# MCU_Comparison.net
KiCad netlist of a schematic drawn in Altium Designer
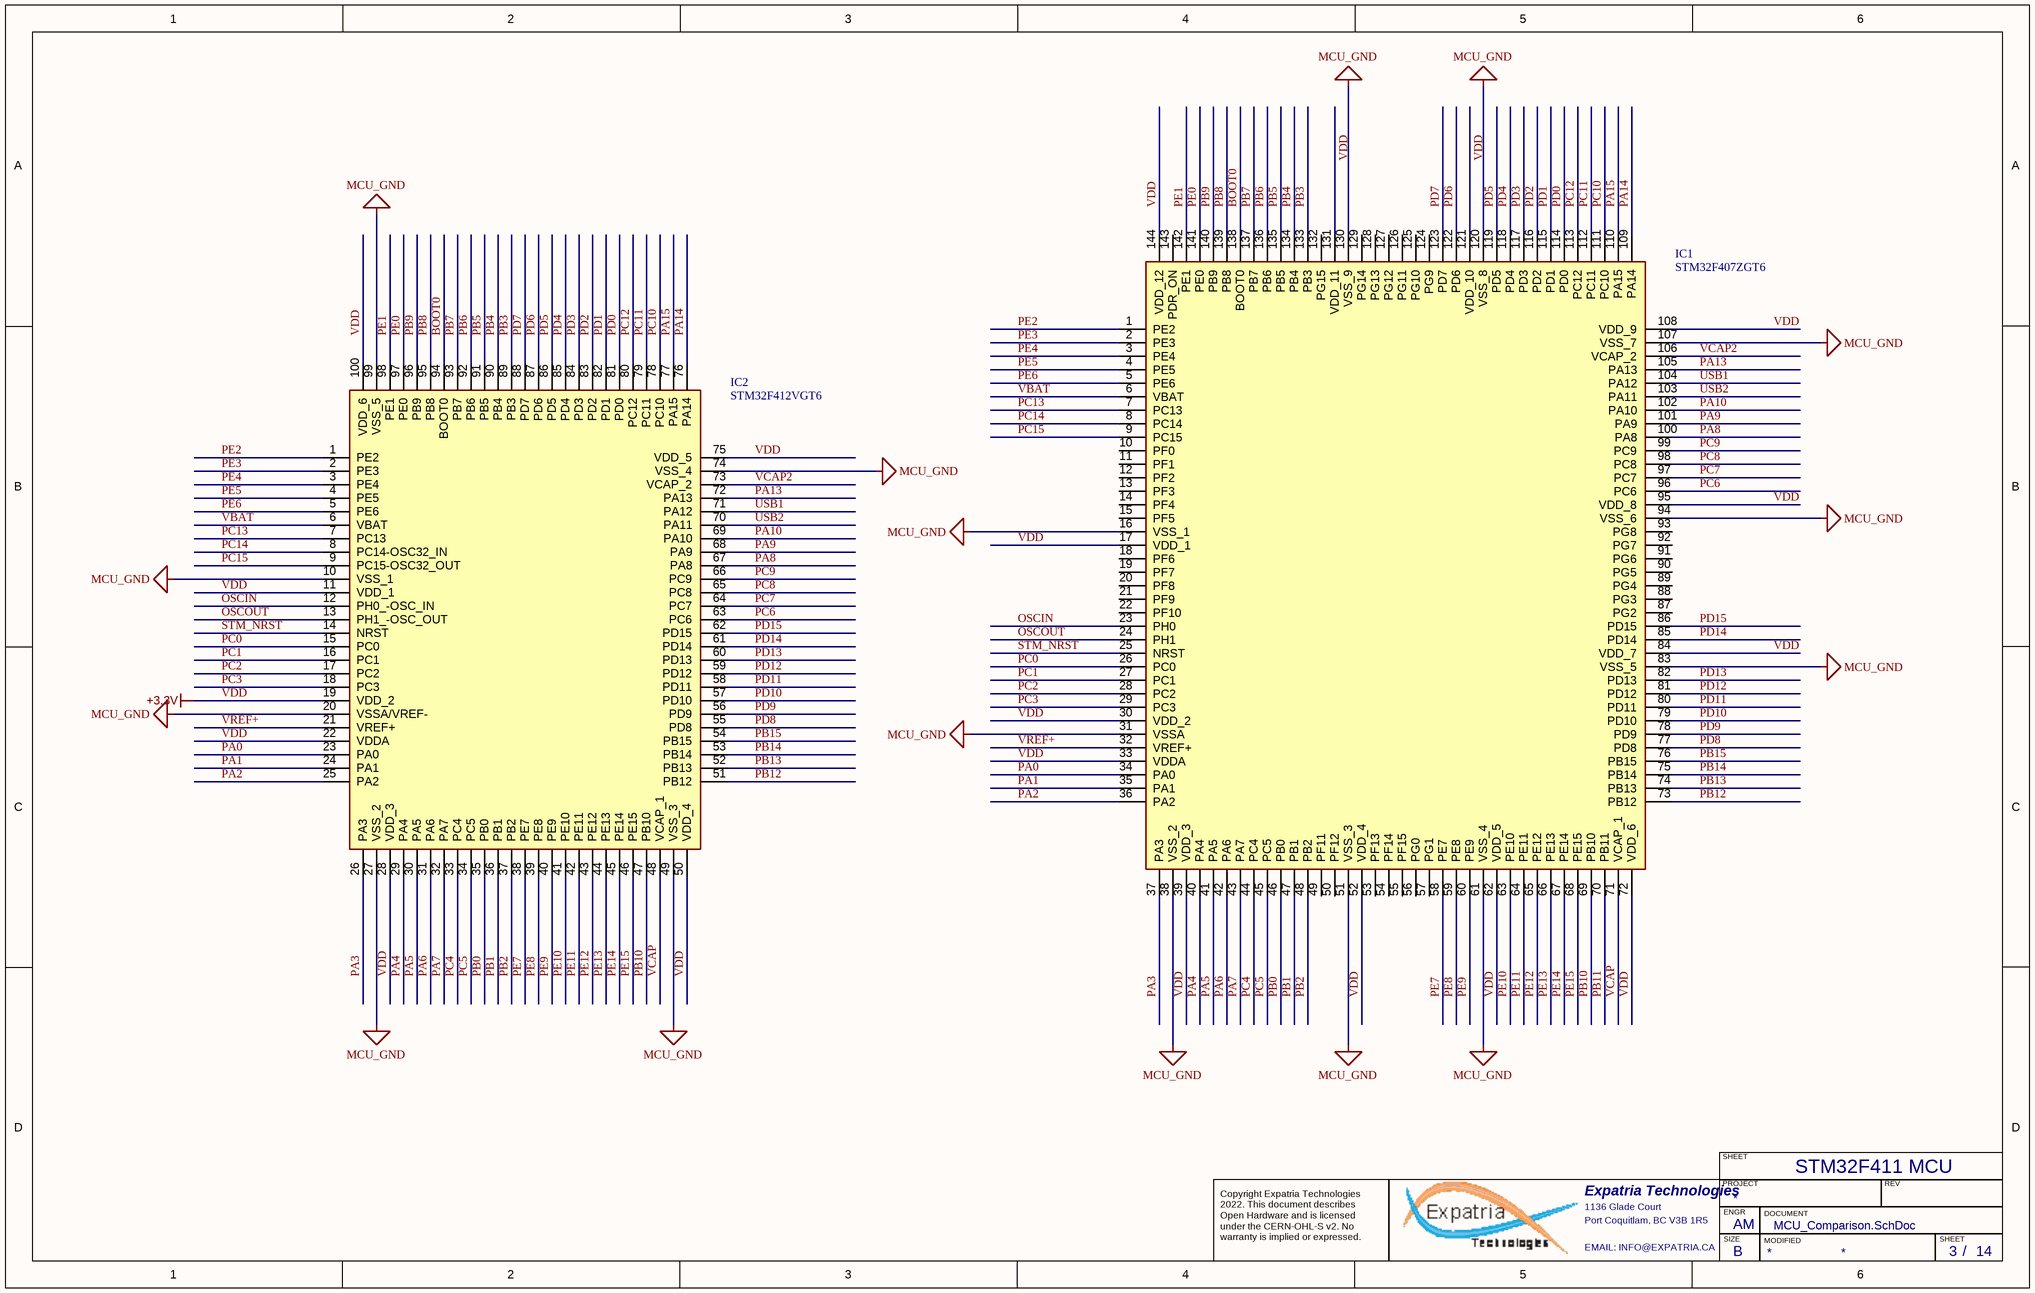
[diagram p0: MCU_Comparison.SchDoc]

(export (version "E")
  (design (tool "Eeschema 10.0.6"))
  (components
    (comp (ref "IC1")
      (value "STM32F407ZGT6")
      (footprint "SamacSys:QFP50P2200X2200X160-144N")
      (description "Integrated Circuit")
      (fields (field (name "MOUSER PART NUMBER") "511-STM32F407ZGT6"))
      (libsource (lib "*") (part "STM32F407ZGT6"))
    )
    (comp (ref "IC2")
      (value "STM32F412VGT6")
      (footprint "SamacSys:QFP50P1600X1600X160-100N")
      (description "Integrated Circuit")
      (fields (field (name "MOUSER PART NUMBER") "511-STM32F412VGT6"))
      (libsource (lib "*") (part "STM32F412VGT6"))
    )
  )
  (nets
    (net (code "1") (name "+3.3V") (class "Default")
      (node (ref "IC1") (pin "108") (pinfunction "VDD_9_108") (pintype "passive"))
      (node (ref "IC1") (pin "121") (pinfunction "VDD_10_121") (pintype "passive"))
      (node (ref "IC1") (pin "131") (pinfunction "VDD_11_131") (pintype "passive"))
      (node (ref "IC1") (pin "144") (pinfunction "VDD_12_144") (pintype "passive"))
      (node (ref "IC1") (pin "17") (pinfunction "VDD_1_17") (pintype "passive"))
      (node (ref "IC1") (pin "30") (pinfunction "VDD_2_30") (pintype "passive"))
      (node (ref "IC1") (pin "33") (pinfunction "VDDA_33") (pintype "passive"))
      (node (ref "IC1") (pin "39") (pinfunction "VDD_3_39") (pintype "passive"))
      (node (ref "IC1") (pin "52") (pinfunction "VDD_4_52") (pintype "passive"))
      (node (ref "IC1") (pin "62") (pinfunction "VDD_5_62") (pintype "passive"))
      (node (ref "IC1") (pin "72") (pinfunction "VDD_6_72") (pintype "passive"))
      (node (ref "IC1") (pin "84") (pinfunction "VDD_7_84") (pintype "passive"))
      (node (ref "IC1") (pin "95") (pinfunction "VDD_8_95") (pintype "passive"))
      (node (ref "IC2") (pin "100") (pinfunction "VDD_6_100") (pintype "passive"))
      (node (ref "IC2") (pin "11") (pinfunction "VDD_1_11") (pintype "passive"))
      (node (ref "IC2") (pin "19") (pinfunction "VDD_2_19") (pintype "passive"))
      (node (ref "IC2") (pin "22") (pinfunction "VDDA_22") (pintype "passive"))
      (node (ref "IC2") (pin "28") (pinfunction "VDD_3_28") (pintype "passive"))
      (node (ref "IC2") (pin "50") (pinfunction "VDD_4_50") (pintype "passive"))
      (node (ref "IC2") (pin "75") (pinfunction "VDD_5_75") (pintype "passive"))
    )
    (net (code "2") (name "/BOOT0") (class "Default")
      (node (ref "IC1") (pin "138") (pinfunction "BOOT0_138") (pintype "passive"))
      (node (ref "IC2") (pin "94") (pinfunction "BOOT0_94") (pintype "passive"))
    )
    (net (code "3") (name "/OSCIN") (class "Default")
      (node (ref "IC1") (pin "23") (pinfunction "PH0_23") (pintype "passive"))
      (node (ref "IC2") (pin "12") (pinfunction "PH0_-OSC_IN_12") (pintype "passive"))
    )
    (net (code "4") (name "/OSCOUT") (class "Default")
      (node (ref "IC1") (pin "24") (pinfunction "PH1_24") (pintype "passive"))
      (node (ref "IC2") (pin "13") (pinfunction "PH1_-OSC_OUT_13") (pintype "passive"))
    )
    (net (code "5") (name "/PA0") (class "Default")
      (node (ref "IC1") (pin "34") (pinfunction "PA0_34") (pintype "passive"))
      (node (ref "IC2") (pin "23") (pinfunction "PA0_23") (pintype "passive"))
    )
    (net (code "6") (name "/PA1") (class "Default")
      (node (ref "IC1") (pin "35") (pinfunction "PA1_35") (pintype "passive"))
      (node (ref "IC2") (pin "24") (pinfunction "PA1_24") (pintype "passive"))
    )
    (net (code "7") (name "/PA2") (class "Default")
      (node (ref "IC1") (pin "36") (pinfunction "PA2_36") (pintype "passive"))
      (node (ref "IC2") (pin "25") (pinfunction "PA2_25") (pintype "passive"))
    )
    (net (code "8") (name "/PA3") (class "Default")
      (node (ref "IC1") (pin "37") (pinfunction "PA3_37") (pintype "passive"))
      (node (ref "IC2") (pin "26") (pinfunction "PA3_26") (pintype "passive"))
    )
    (net (code "9") (name "/PA4") (class "Default")
      (node (ref "IC1") (pin "40") (pinfunction "PA4_40") (pintype "passive"))
      (node (ref "IC2") (pin "29") (pinfunction "PA4_29") (pintype "passive"))
    )
    (net (code "10") (name "/PA5") (class "Default")
      (node (ref "IC1") (pin "41") (pinfunction "PA5_41") (pintype "passive"))
      (node (ref "IC2") (pin "30") (pinfunction "PA5_30") (pintype "passive"))
    )
    (net (code "11") (name "/PA6") (class "Default")
      (node (ref "IC1") (pin "42") (pinfunction "PA6_42") (pintype "passive"))
      (node (ref "IC2") (pin "31") (pinfunction "PA6_31") (pintype "passive"))
    )
    (net (code "12") (name "/PA7") (class "Default")
      (node (ref "IC1") (pin "43") (pinfunction "PA7_43") (pintype "passive"))
      (node (ref "IC2") (pin "32") (pinfunction "PA7_32") (pintype "passive"))
    )
    (net (code "13") (name "/PA8") (class "Default")
      (node (ref "IC1") (pin "100") (pinfunction "PA8_100") (pintype "passive"))
      (node (ref "IC2") (pin "67") (pinfunction "PA8_67") (pintype "passive"))
    )
    (net (code "14") (name "/PA9") (class "Default")
      (node (ref "IC1") (pin "101") (pinfunction "PA9_101") (pintype "passive"))
      (node (ref "IC2") (pin "68") (pinfunction "PA9_68") (pintype "passive"))
    )
    (net (code "15") (name "/PA10") (class "Default")
      (node (ref "IC1") (pin "102") (pinfunction "PA10_102") (pintype "passive"))
      (node (ref "IC2") (pin "69") (pinfunction "PA10_69") (pintype "passive"))
    )
    (net (code "16") (name "/PA13") (class "Default")
      (node (ref "IC1") (pin "105") (pinfunction "PA13_105") (pintype "passive"))
      (node (ref "IC2") (pin "72") (pinfunction "PA13_72") (pintype "passive"))
    )
    (net (code "17") (name "/PA14") (class "Default")
      (node (ref "IC1") (pin "109") (pinfunction "PA14_109") (pintype "passive"))
      (node (ref "IC2") (pin "76") (pinfunction "PA14_76") (pintype "passive"))
    )
    (net (code "18") (name "/PA15") (class "Default")
      (node (ref "IC1") (pin "110") (pinfunction "PA15_110") (pintype "passive"))
      (node (ref "IC2") (pin "77") (pinfunction "PA15_77") (pintype "passive"))
    )
    (net (code "19") (name "/PB0") (class "Default")
      (node (ref "IC1") (pin "46") (pinfunction "PB0_46") (pintype "passive"))
      (node (ref "IC2") (pin "35") (pinfunction "PB0_35") (pintype "passive"))
    )
    (net (code "20") (name "/PB1") (class "Default")
      (node (ref "IC1") (pin "47") (pinfunction "PB1_47") (pintype "passive"))
      (node (ref "IC2") (pin "36") (pinfunction "PB1_36") (pintype "passive"))
    )
    (net (code "21") (name "/PB2") (class "Default")
      (node (ref "IC1") (pin "48") (pinfunction "PB2_48") (pintype "passive"))
      (node (ref "IC2") (pin "37") (pinfunction "PB2_37") (pintype "passive"))
    )
    (net (code "22") (name "/PB3") (class "Default")
      (node (ref "IC1") (pin "133") (pinfunction "PB3_133") (pintype "passive"))
      (node (ref "IC2") (pin "89") (pinfunction "PB3_89") (pintype "passive"))
    )
    (net (code "23") (name "/PB4") (class "Default")
      (node (ref "IC1") (pin "134") (pinfunction "PB4_134") (pintype "passive"))
      (node (ref "IC2") (pin "90") (pinfunction "PB4_90") (pintype "passive"))
    )
    (net (code "24") (name "/PB5") (class "Default")
      (node (ref "IC1") (pin "135") (pinfunction "PB5_135") (pintype "passive"))
      (node (ref "IC2") (pin "91") (pinfunction "PB5_91") (pintype "passive"))
    )
    (net (code "25") (name "/PB6") (class "Default")
      (node (ref "IC1") (pin "136") (pinfunction "PB6_136") (pintype "passive"))
      (node (ref "IC2") (pin "92") (pinfunction "PB6_92") (pintype "passive"))
    )
    (net (code "26") (name "/PB7") (class "Default")
      (node (ref "IC1") (pin "137") (pinfunction "PB7_137") (pintype "passive"))
      (node (ref "IC2") (pin "93") (pinfunction "PB7_93") (pintype "passive"))
    )
    (net (code "27") (name "/PB8") (class "Default")
      (node (ref "IC1") (pin "139") (pinfunction "PB8_139") (pintype "passive"))
      (node (ref "IC2") (pin "95") (pinfunction "PB8_95") (pintype "passive"))
    )
    (net (code "28") (name "/PB9") (class "Default")
      (node (ref "IC1") (pin "140") (pinfunction "PB9_140") (pintype "passive"))
      (node (ref "IC2") (pin "96") (pinfunction "PB9_96") (pintype "passive"))
    )
    (net (code "29") (name "/PB10") (class "Default")
      (node (ref "IC1") (pin "69") (pinfunction "PB10_69") (pintype "passive"))
      (node (ref "IC2") (pin "47") (pinfunction "PB10_47") (pintype "passive"))
    )
    (net (code "30") (name "/PB11") (class "Default")
      (node (ref "IC1") (pin "70") (pinfunction "PB11_70") (pintype "passive"))
    )
    (net (code "31") (name "/PB12") (class "Default")
      (node (ref "IC1") (pin "73") (pinfunction "PB12_73") (pintype "passive"))
      (node (ref "IC2") (pin "51") (pinfunction "PB12_51") (pintype "passive"))
    )
    (net (code "32") (name "/PB13") (class "Default")
      (node (ref "IC1") (pin "74") (pinfunction "PB13_74") (pintype "passive"))
      (node (ref "IC2") (pin "52") (pinfunction "PB13_52") (pintype "passive"))
    )
    (net (code "33") (name "/PB14") (class "Default")
      (node (ref "IC1") (pin "75") (pinfunction "PB14_75") (pintype "passive"))
      (node (ref "IC2") (pin "53") (pinfunction "PB14_53") (pintype "passive"))
    )
    (net (code "34") (name "/PB15") (class "Default")
      (node (ref "IC1") (pin "76") (pinfunction "PB15_76") (pintype "passive"))
      (node (ref "IC2") (pin "54") (pinfunction "PB15_54") (pintype "passive"))
    )
    (net (code "35") (name "/PC0") (class "Default")
      (node (ref "IC1") (pin "26") (pinfunction "PC0_26") (pintype "passive"))
      (node (ref "IC2") (pin "15") (pinfunction "PC0_15") (pintype "passive"))
    )
    (net (code "36") (name "/PC1") (class "Default")
      (node (ref "IC1") (pin "27") (pinfunction "PC1_27") (pintype "passive"))
      (node (ref "IC2") (pin "16") (pinfunction "PC1_16") (pintype "passive"))
    )
    (net (code "37") (name "/PC2") (class "Default")
      (node (ref "IC1") (pin "28") (pinfunction "PC2_28") (pintype "passive"))
      (node (ref "IC2") (pin "17") (pinfunction "PC2_17") (pintype "passive"))
    )
    (net (code "38") (name "/PC3") (class "Default")
      (node (ref "IC1") (pin "29") (pinfunction "PC3_29") (pintype "passive"))
      (node (ref "IC2") (pin "18") (pinfunction "PC3_18") (pintype "passive"))
    )
    (net (code "39") (name "/PC4") (class "Default")
      (node (ref "IC1") (pin "44") (pinfunction "PC4_44") (pintype "passive"))
      (node (ref "IC2") (pin "33") (pinfunction "PC4_33") (pintype "passive"))
    )
    (net (code "40") (name "/PC5") (class "Default")
      (node (ref "IC1") (pin "45") (pinfunction "PC5_45") (pintype "passive"))
      (node (ref "IC2") (pin "34") (pinfunction "PC5_34") (pintype "passive"))
    )
    (net (code "41") (name "/PC6") (class "Default")
      (node (ref "IC1") (pin "96") (pinfunction "PC6_96") (pintype "passive"))
      (node (ref "IC2") (pin "63") (pinfunction "PC6_63") (pintype "passive"))
    )
    (net (code "42") (name "/PC7") (class "Default")
      (node (ref "IC1") (pin "97") (pinfunction "PC7_97") (pintype "passive"))
      (node (ref "IC2") (pin "64") (pinfunction "PC7_64") (pintype "passive"))
    )
    (net (code "43") (name "/PC8") (class "Default")
      (node (ref "IC1") (pin "98") (pinfunction "PC8_98") (pintype "passive"))
      (node (ref "IC2") (pin "65") (pinfunction "PC8_65") (pintype "passive"))
    )
    (net (code "44") (name "/PC9") (class "Default")
      (node (ref "IC1") (pin "99") (pinfunction "PC9_99") (pintype "passive"))
      (node (ref "IC2") (pin "66") (pinfunction "PC9_66") (pintype "passive"))
    )
    (net (code "45") (name "/PC10") (class "Default")
      (node (ref "IC1") (pin "111") (pinfunction "PC10_111") (pintype "passive"))
      (node (ref "IC2") (pin "78") (pinfunction "PC10_78") (pintype "passive"))
    )
    (net (code "46") (name "/PC11") (class "Default")
      (node (ref "IC1") (pin "112") (pinfunction "PC11_112") (pintype "passive"))
      (node (ref "IC2") (pin "79") (pinfunction "PC11_79") (pintype "passive"))
    )
    (net (code "47") (name "/PC12") (class "Default")
      (node (ref "IC1") (pin "113") (pinfunction "PC12_113") (pintype "passive"))
      (node (ref "IC2") (pin "80") (pinfunction "PC12_80") (pintype "passive"))
    )
    (net (code "48") (name "/PC13") (class "Default")
      (node (ref "IC1") (pin "7") (pinfunction "PC13_7") (pintype "passive"))
      (node (ref "IC2") (pin "7") (pinfunction "PC13_7") (pintype "passive"))
    )
    (net (code "49") (name "/PC14") (class "Default")
      (node (ref "IC1") (pin "8") (pinfunction "PC14_8") (pintype "passive"))
      (node (ref "IC2") (pin "8") (pinfunction "PC14-OSC32_IN_8") (pintype "passive"))
    )
    (net (code "50") (name "/PC15") (class "Default")
      (node (ref "IC1") (pin "9") (pinfunction "PC15_9") (pintype "passive"))
      (node (ref "IC2") (pin "9") (pinfunction "PC15-OSC32_OUT_9") (pintype "passive"))
    )
    (net (code "51") (name "/PD0") (class "Default")
      (node (ref "IC1") (pin "114") (pinfunction "PD0_114") (pintype "passive"))
      (node (ref "IC2") (pin "81") (pinfunction "PD0_81") (pintype "passive"))
    )
    (net (code "52") (name "/PD1") (class "Default")
      (node (ref "IC1") (pin "115") (pinfunction "PD1_115") (pintype "passive"))
      (node (ref "IC2") (pin "82") (pinfunction "PD1_82") (pintype "passive"))
    )
    (net (code "53") (name "/PD2") (class "Default")
      (node (ref "IC1") (pin "116") (pinfunction "PD2_116") (pintype "passive"))
      (node (ref "IC2") (pin "83") (pinfunction "PD2_83") (pintype "passive"))
    )
    (net (code "54") (name "/PD3") (class "Default")
      (node (ref "IC1") (pin "117") (pinfunction "PD3_117") (pintype "passive"))
      (node (ref "IC2") (pin "84") (pinfunction "PD3_84") (pintype "passive"))
    )
    (net (code "55") (name "/PD4") (class "Default")
      (node (ref "IC1") (pin "118") (pinfunction "PD4_118") (pintype "passive"))
      (node (ref "IC2") (pin "85") (pinfunction "PD4_85") (pintype "passive"))
    )
    (net (code "56") (name "/PD5") (class "Default")
      (node (ref "IC1") (pin "119") (pinfunction "PD5_119") (pintype "passive"))
      (node (ref "IC2") (pin "86") (pinfunction "PD5_86") (pintype "passive"))
    )
    (net (code "57") (name "/PD6") (class "Default")
      (node (ref "IC1") (pin "122") (pinfunction "PD6_122") (pintype "passive"))
      (node (ref "IC2") (pin "87") (pinfunction "PD6_87") (pintype "passive"))
    )
    (net (code "58") (name "/PD7") (class "Default")
      (node (ref "IC1") (pin "123") (pinfunction "PD7_123") (pintype "passive"))
      (node (ref "IC2") (pin "88") (pinfunction "PD7_88") (pintype "passive"))
    )
    (net (code "59") (name "/PD8") (class "Default")
      (node (ref "IC1") (pin "77") (pinfunction "PD8_77") (pintype "passive"))
      (node (ref "IC2") (pin "55") (pinfunction "PD8_55") (pintype "passive"))
    )
    (net (code "60") (name "/PD9") (class "Default")
      (node (ref "IC1") (pin "78") (pinfunction "PD9_78") (pintype "passive"))
      (node (ref "IC2") (pin "56") (pinfunction "PD9_56") (pintype "passive"))
    )
    (net (code "61") (name "/PD10") (class "Default")
      (node (ref "IC1") (pin "79") (pinfunction "PD10_79") (pintype "passive"))
      (node (ref "IC2") (pin "57") (pinfunction "PD10_57") (pintype "passive"))
    )
    (net (code "62") (name "/PD11") (class "Default")
      (node (ref "IC1") (pin "80") (pinfunction "PD11_80") (pintype "passive"))
      (node (ref "IC2") (pin "58") (pinfunction "PD11_58") (pintype "passive"))
    )
    (net (code "63") (name "/PD12") (class "Default")
      (node (ref "IC1") (pin "81") (pinfunction "PD12_81") (pintype "passive"))
      (node (ref "IC2") (pin "59") (pinfunction "PD12_59") (pintype "passive"))
    )
    (net (code "64") (name "/PD13") (class "Default")
      (node (ref "IC1") (pin "82") (pinfunction "PD13_82") (pintype "passive"))
      (node (ref "IC2") (pin "60") (pinfunction "PD13_60") (pintype "passive"))
    )
    (net (code "65") (name "/PD14") (class "Default")
      (node (ref "IC1") (pin "85") (pinfunction "PD14_85") (pintype "passive"))
      (node (ref "IC2") (pin "61") (pinfunction "PD14_61") (pintype "passive"))
    )
    (net (code "66") (name "/PD15") (class "Default")
      (node (ref "IC1") (pin "86") (pinfunction "PD15_86") (pintype "passive"))
      (node (ref "IC2") (pin "62") (pinfunction "PD15_62") (pintype "passive"))
    )
    (net (code "67") (name "/PE0") (class "Default")
      (node (ref "IC1") (pin "141") (pinfunction "PE0_141") (pintype "passive"))
      (node (ref "IC2") (pin "97") (pinfunction "PE0_97") (pintype "passive"))
    )
    (net (code "68") (name "/PE1") (class "Default")
      (node (ref "IC1") (pin "142") (pinfunction "PE1_142") (pintype "passive"))
      (node (ref "IC2") (pin "98") (pinfunction "PE1_98") (pintype "passive"))
    )
    (net (code "69") (name "/PE2") (class "Default")
      (node (ref "IC1") (pin "1") (pinfunction "PE2_1") (pintype "passive"))
      (node (ref "IC2") (pin "1") (pinfunction "PE2_1") (pintype "passive"))
    )
    (net (code "70") (name "/PE3") (class "Default")
      (node (ref "IC1") (pin "2") (pinfunction "PE3_2") (pintype "passive"))
      (node (ref "IC2") (pin "2") (pinfunction "PE3_2") (pintype "passive"))
    )
    (net (code "71") (name "/PE4") (class "Default")
      (node (ref "IC1") (pin "3") (pinfunction "PE4_3") (pintype "passive"))
      (node (ref "IC2") (pin "3") (pinfunction "PE4_3") (pintype "passive"))
    )
    (net (code "72") (name "/PE5") (class "Default")
      (node (ref "IC1") (pin "4") (pinfunction "PE5_4") (pintype "passive"))
      (node (ref "IC2") (pin "4") (pinfunction "PE5_4") (pintype "passive"))
    )
    (net (code "73") (name "/PE6") (class "Default")
      (node (ref "IC1") (pin "5") (pinfunction "PE6_5") (pintype "passive"))
      (node (ref "IC2") (pin "5") (pinfunction "PE6_5") (pintype "passive"))
    )
    (net (code "74") (name "/PE7") (class "Default")
      (node (ref "IC1") (pin "58") (pinfunction "PE7_58") (pintype "passive"))
      (node (ref "IC2") (pin "38") (pinfunction "PE7_38") (pintype "passive"))
    )
    (net (code "75") (name "/PE8") (class "Default")
      (node (ref "IC1") (pin "59") (pinfunction "PE8_59") (pintype "passive"))
      (node (ref "IC2") (pin "39") (pinfunction "PE8_39") (pintype "passive"))
    )
    (net (code "76") (name "/PE9") (class "Default")
      (node (ref "IC1") (pin "60") (pinfunction "PE9_60") (pintype "passive"))
      (node (ref "IC2") (pin "40") (pinfunction "PE9_40") (pintype "passive"))
    )
    (net (code "77") (name "/PE10") (class "Default")
      (node (ref "IC1") (pin "63") (pinfunction "PE10_63") (pintype "passive"))
      (node (ref "IC2") (pin "41") (pinfunction "PE10_41") (pintype "passive"))
    )
    (net (code "78") (name "/PE11") (class "Default")
      (node (ref "IC1") (pin "64") (pinfunction "PE11_64") (pintype "passive"))
      (node (ref "IC2") (pin "42") (pinfunction "PE11_42") (pintype "passive"))
    )
    (net (code "79") (name "/PE12") (class "Default")
      (node (ref "IC1") (pin "65") (pinfunction "PE12_65") (pintype "passive"))
      (node (ref "IC2") (pin "43") (pinfunction "PE12_43") (pintype "passive"))
    )
    (net (code "80") (name "/PE13") (class "Default")
      (node (ref "IC1") (pin "66") (pinfunction "PE13_66") (pintype "passive"))
      (node (ref "IC2") (pin "44") (pinfunction "PE13_44") (pintype "passive"))
    )
    (net (code "81") (name "/PE14") (class "Default")
      (node (ref "IC1") (pin "67") (pinfunction "PE14_67") (pintype "passive"))
      (node (ref "IC2") (pin "45") (pinfunction "PE14_45") (pintype "passive"))
    )
    (net (code "82") (name "/PE15") (class "Default")
      (node (ref "IC1") (pin "68") (pinfunction "PE15_68") (pintype "passive"))
      (node (ref "IC2") (pin "46") (pinfunction "PE15_46") (pintype "passive"))
    )
    (net (code "83") (name "/STM_NRST") (class "Default")
      (node (ref "IC1") (pin "25") (pinfunction "NRST_25") (pintype "passive"))
      (node (ref "IC2") (pin "14") (pinfunction "NRST_14") (pintype "passive"))
    )
    (net (code "84") (name "/USB1") (class "Default")
      (node (ref "IC1") (pin "104") (pinfunction "PA12_104") (pintype "passive"))
      (node (ref "IC2") (pin "71") (pinfunction "PA12_71") (pintype "passive"))
    )
    (net (code "85") (name "/USB2") (class "Default")
      (node (ref "IC1") (pin "103") (pinfunction "PA11_103") (pintype "passive"))
      (node (ref "IC2") (pin "70") (pinfunction "PA11_70") (pintype "passive"))
    )
    (net (code "86") (name "/VBAT") (class "Default")
      (node (ref "IC1") (pin "6") (pinfunction "VBAT_6") (pintype "passive"))
      (node (ref "IC2") (pin "6") (pinfunction "VBAT_6") (pintype "passive"))
    )
    (net (code "87") (name "/VCAP") (class "Default")
      (node (ref "IC1") (pin "71") (pinfunction "VCAP_1_71") (pintype "passive"))
      (node (ref "IC2") (pin "48") (pinfunction "VCAP_1_48") (pintype "passive"))
    )
    (net (code "88") (name "/VCAP2") (class "Default")
      (node (ref "IC1") (pin "106") (pinfunction "VCAP_2_106") (pintype "passive"))
      (node (ref "IC2") (pin "73") (pinfunction "VCAP_2_73") (pintype "passive"))
    )
    (net (code "89") (name "/VREF+") (class "Default")
      (node (ref "IC1") (pin "32") (pinfunction "VREF+_32") (pintype "passive"))
      (node (ref "IC2") (pin "21") (pinfunction "VREF+_21") (pintype "passive"))
    )
    (net (code "90") (name "MCU_GND") (class "Default")
      (node (ref "IC1") (pin "107") (pinfunction "VSS_7_107") (pintype "passive"))
      (node (ref "IC1") (pin "120") (pinfunction "VSS_8_120") (pintype "passive"))
      (node (ref "IC1") (pin "130") (pinfunction "VSS_9_130") (pintype "passive"))
      (node (ref "IC1") (pin "16") (pinfunction "VSS_1_16") (pintype "passive"))
      (node (ref "IC1") (pin "31") (pinfunction "VSSA_31") (pintype "passive"))
      (node (ref "IC1") (pin "38") (pinfunction "VSS_2_38") (pintype "passive"))
      (node (ref "IC1") (pin "51") (pinfunction "VSS_3_51") (pintype "passive"))
      (node (ref "IC1") (pin "61") (pinfunction "VSS_4_61") (pintype "passive"))
      (node (ref "IC1") (pin "83") (pinfunction "VSS_5_83") (pintype "passive"))
      (node (ref "IC1") (pin "94") (pinfunction "VSS_6_94") (pintype "passive"))
      (node (ref "IC2") (pin "10") (pinfunction "VSS_1_10") (pintype "passive"))
      (node (ref "IC2") (pin "20") (pinfunction "VSSA/VREF-_20") (pintype "passive"))
      (node (ref "IC2") (pin "27") (pinfunction "VSS_2_27") (pintype "passive"))
      (node (ref "IC2") (pin "49") (pinfunction "VSS_3_49") (pintype "passive"))
      (node (ref "IC2") (pin "74") (pinfunction "VSS_4_74") (pintype "passive"))
      (node (ref "IC2") (pin "99") (pinfunction "VSS_5_99") (pintype "passive"))
    )
    (net (code "91") (name "unconnected-(IC1-PDR_ON-Pad143)") (class "Default")
      (node (ref "IC1") (pin "143") (pinfunction "PDR_ON_143") (pintype "passive"))
    )
    (net (code "92") (name "unconnected-(IC1-PF0-Pad10)") (class "Default")
      (node (ref "IC1") (pin "10") (pinfunction "PF0_10") (pintype "passive"))
    )
    (net (code "93") (name "unconnected-(IC1-PF1-Pad11)") (class "Default")
      (node (ref "IC1") (pin "11") (pinfunction "PF1_11") (pintype "passive"))
    )
    (net (code "94") (name "unconnected-(IC1-PF2-Pad12)") (class "Default")
      (node (ref "IC1") (pin "12") (pinfunction "PF2_12") (pintype "passive"))
    )
    (net (code "95") (name "unconnected-(IC1-PF3-Pad13)") (class "Default")
      (node (ref "IC1") (pin "13") (pinfunction "PF3_13") (pintype "passive"))
    )
    (net (code "96") (name "unconnected-(IC1-PF4-Pad14)") (class "Default")
      (node (ref "IC1") (pin "14") (pinfunction "PF4_14") (pintype "passive"))
    )
    (net (code "97") (name "unconnected-(IC1-PF5-Pad15)") (class "Default")
      (node (ref "IC1") (pin "15") (pinfunction "PF5_15") (pintype "passive"))
    )
    (net (code "98") (name "unconnected-(IC1-PF6-Pad18)") (class "Default")
      (node (ref "IC1") (pin "18") (pinfunction "PF6_18") (pintype "passive"))
    )
    (net (code "99") (name "unconnected-(IC1-PF7-Pad19)") (class "Default")
      (node (ref "IC1") (pin "19") (pinfunction "PF7_19") (pintype "passive"))
    )
    (net (code "100") (name "unconnected-(IC1-PF8-Pad20)") (class "Default")
      (node (ref "IC1") (pin "20") (pinfunction "PF8_20") (pintype "passive"))
    )
    (net (code "101") (name "unconnected-(IC1-PF9-Pad21)") (class "Default")
      (node (ref "IC1") (pin "21") (pinfunction "PF9_21") (pintype "passive"))
    )
    (net (code "102") (name "unconnected-(IC1-PF10-Pad22)") (class "Default")
      (node (ref "IC1") (pin "22") (pinfunction "PF10_22") (pintype "passive"))
    )
    (net (code "103") (name "unconnected-(IC1-PF11-Pad49)") (class "Default")
      (node (ref "IC1") (pin "49") (pinfunction "PF11_49") (pintype "passive"))
    )
    (net (code "104") (name "unconnected-(IC1-PF12-Pad50)") (class "Default")
      (node (ref "IC1") (pin "50") (pinfunction "PF12_50") (pintype "passive"))
    )
    (net (code "105") (name "unconnected-(IC1-PF13-Pad53)") (class "Default")
      (node (ref "IC1") (pin "53") (pinfunction "PF13_53") (pintype "passive"))
    )
    (net (code "106") (name "unconnected-(IC1-PF14-Pad54)") (class "Default")
      (node (ref "IC1") (pin "54") (pinfunction "PF14_54") (pintype "passive"))
    )
    (net (code "107") (name "unconnected-(IC1-PF15-Pad55)") (class "Default")
      (node (ref "IC1") (pin "55") (pinfunction "PF15_55") (pintype "passive"))
    )
    (net (code "108") (name "unconnected-(IC1-PG0-Pad56)") (class "Default")
      (node (ref "IC1") (pin "56") (pinfunction "PG0_56") (pintype "passive"))
    )
    (net (code "109") (name "unconnected-(IC1-PG1-Pad57)") (class "Default")
      (node (ref "IC1") (pin "57") (pinfunction "PG1_57") (pintype "passive"))
    )
    (net (code "110") (name "unconnected-(IC1-PG2-Pad87)") (class "Default")
      (node (ref "IC1") (pin "87") (pinfunction "PG2_87") (pintype "passive"))
    )
    (net (code "111") (name "unconnected-(IC1-PG3-Pad88)") (class "Default")
      (node (ref "IC1") (pin "88") (pinfunction "PG3_88") (pintype "passive"))
    )
    (net (code "112") (name "unconnected-(IC1-PG4-Pad89)") (class "Default")
      (node (ref "IC1") (pin "89") (pinfunction "PG4_89") (pintype "passive"))
    )
    (net (code "113") (name "unconnected-(IC1-PG5-Pad90)") (class "Default")
      (node (ref "IC1") (pin "90") (pinfunction "PG5_90") (pintype "passive"))
    )
    (net (code "114") (name "unconnected-(IC1-PG6-Pad91)") (class "Default")
      (node (ref "IC1") (pin "91") (pinfunction "PG6_91") (pintype "passive"))
    )
    (net (code "115") (name "unconnected-(IC1-PG7-Pad92)") (class "Default")
      (node (ref "IC1") (pin "92") (pinfunction "PG7_92") (pintype "passive"))
    )
    (net (code "116") (name "unconnected-(IC1-PG8-Pad93)") (class "Default")
      (node (ref "IC1") (pin "93") (pinfunction "PG8_93") (pintype "passive"))
    )
    (net (code "117") (name "unconnected-(IC1-PG9-Pad124)") (class "Default")
      (node (ref "IC1") (pin "124") (pinfunction "PG9_124") (pintype "passive"))
    )
    (net (code "118") (name "unconnected-(IC1-PG10-Pad125)") (class "Default")
      (node (ref "IC1") (pin "125") (pinfunction "PG10_125") (pintype "passive"))
    )
    (net (code "119") (name "unconnected-(IC1-PG11-Pad126)") (class "Default")
      (node (ref "IC1") (pin "126") (pinfunction "PG11_126") (pintype "passive"))
    )
    (net (code "120") (name "unconnected-(IC1-PG12-Pad127)") (class "Default")
      (node (ref "IC1") (pin "127") (pinfunction "PG12_127") (pintype "passive"))
    )
    (net (code "121") (name "unconnected-(IC1-PG13-Pad128)") (class "Default")
      (node (ref "IC1") (pin "128") (pinfunction "PG13_128") (pintype "passive"))
    )
    (net (code "122") (name "unconnected-(IC1-PG14-Pad129)") (class "Default")
      (node (ref "IC1") (pin "129") (pinfunction "PG14_129") (pintype "passive"))
    )
    (net (code "123") (name "unconnected-(IC1-PG15-Pad132)") (class "Default")
      (node (ref "IC1") (pin "132") (pinfunction "PG15_132") (pintype "passive"))
    )
  )
)
